# 2.net
KiCad netlist of a schematic drawn in EasyEDA Pro
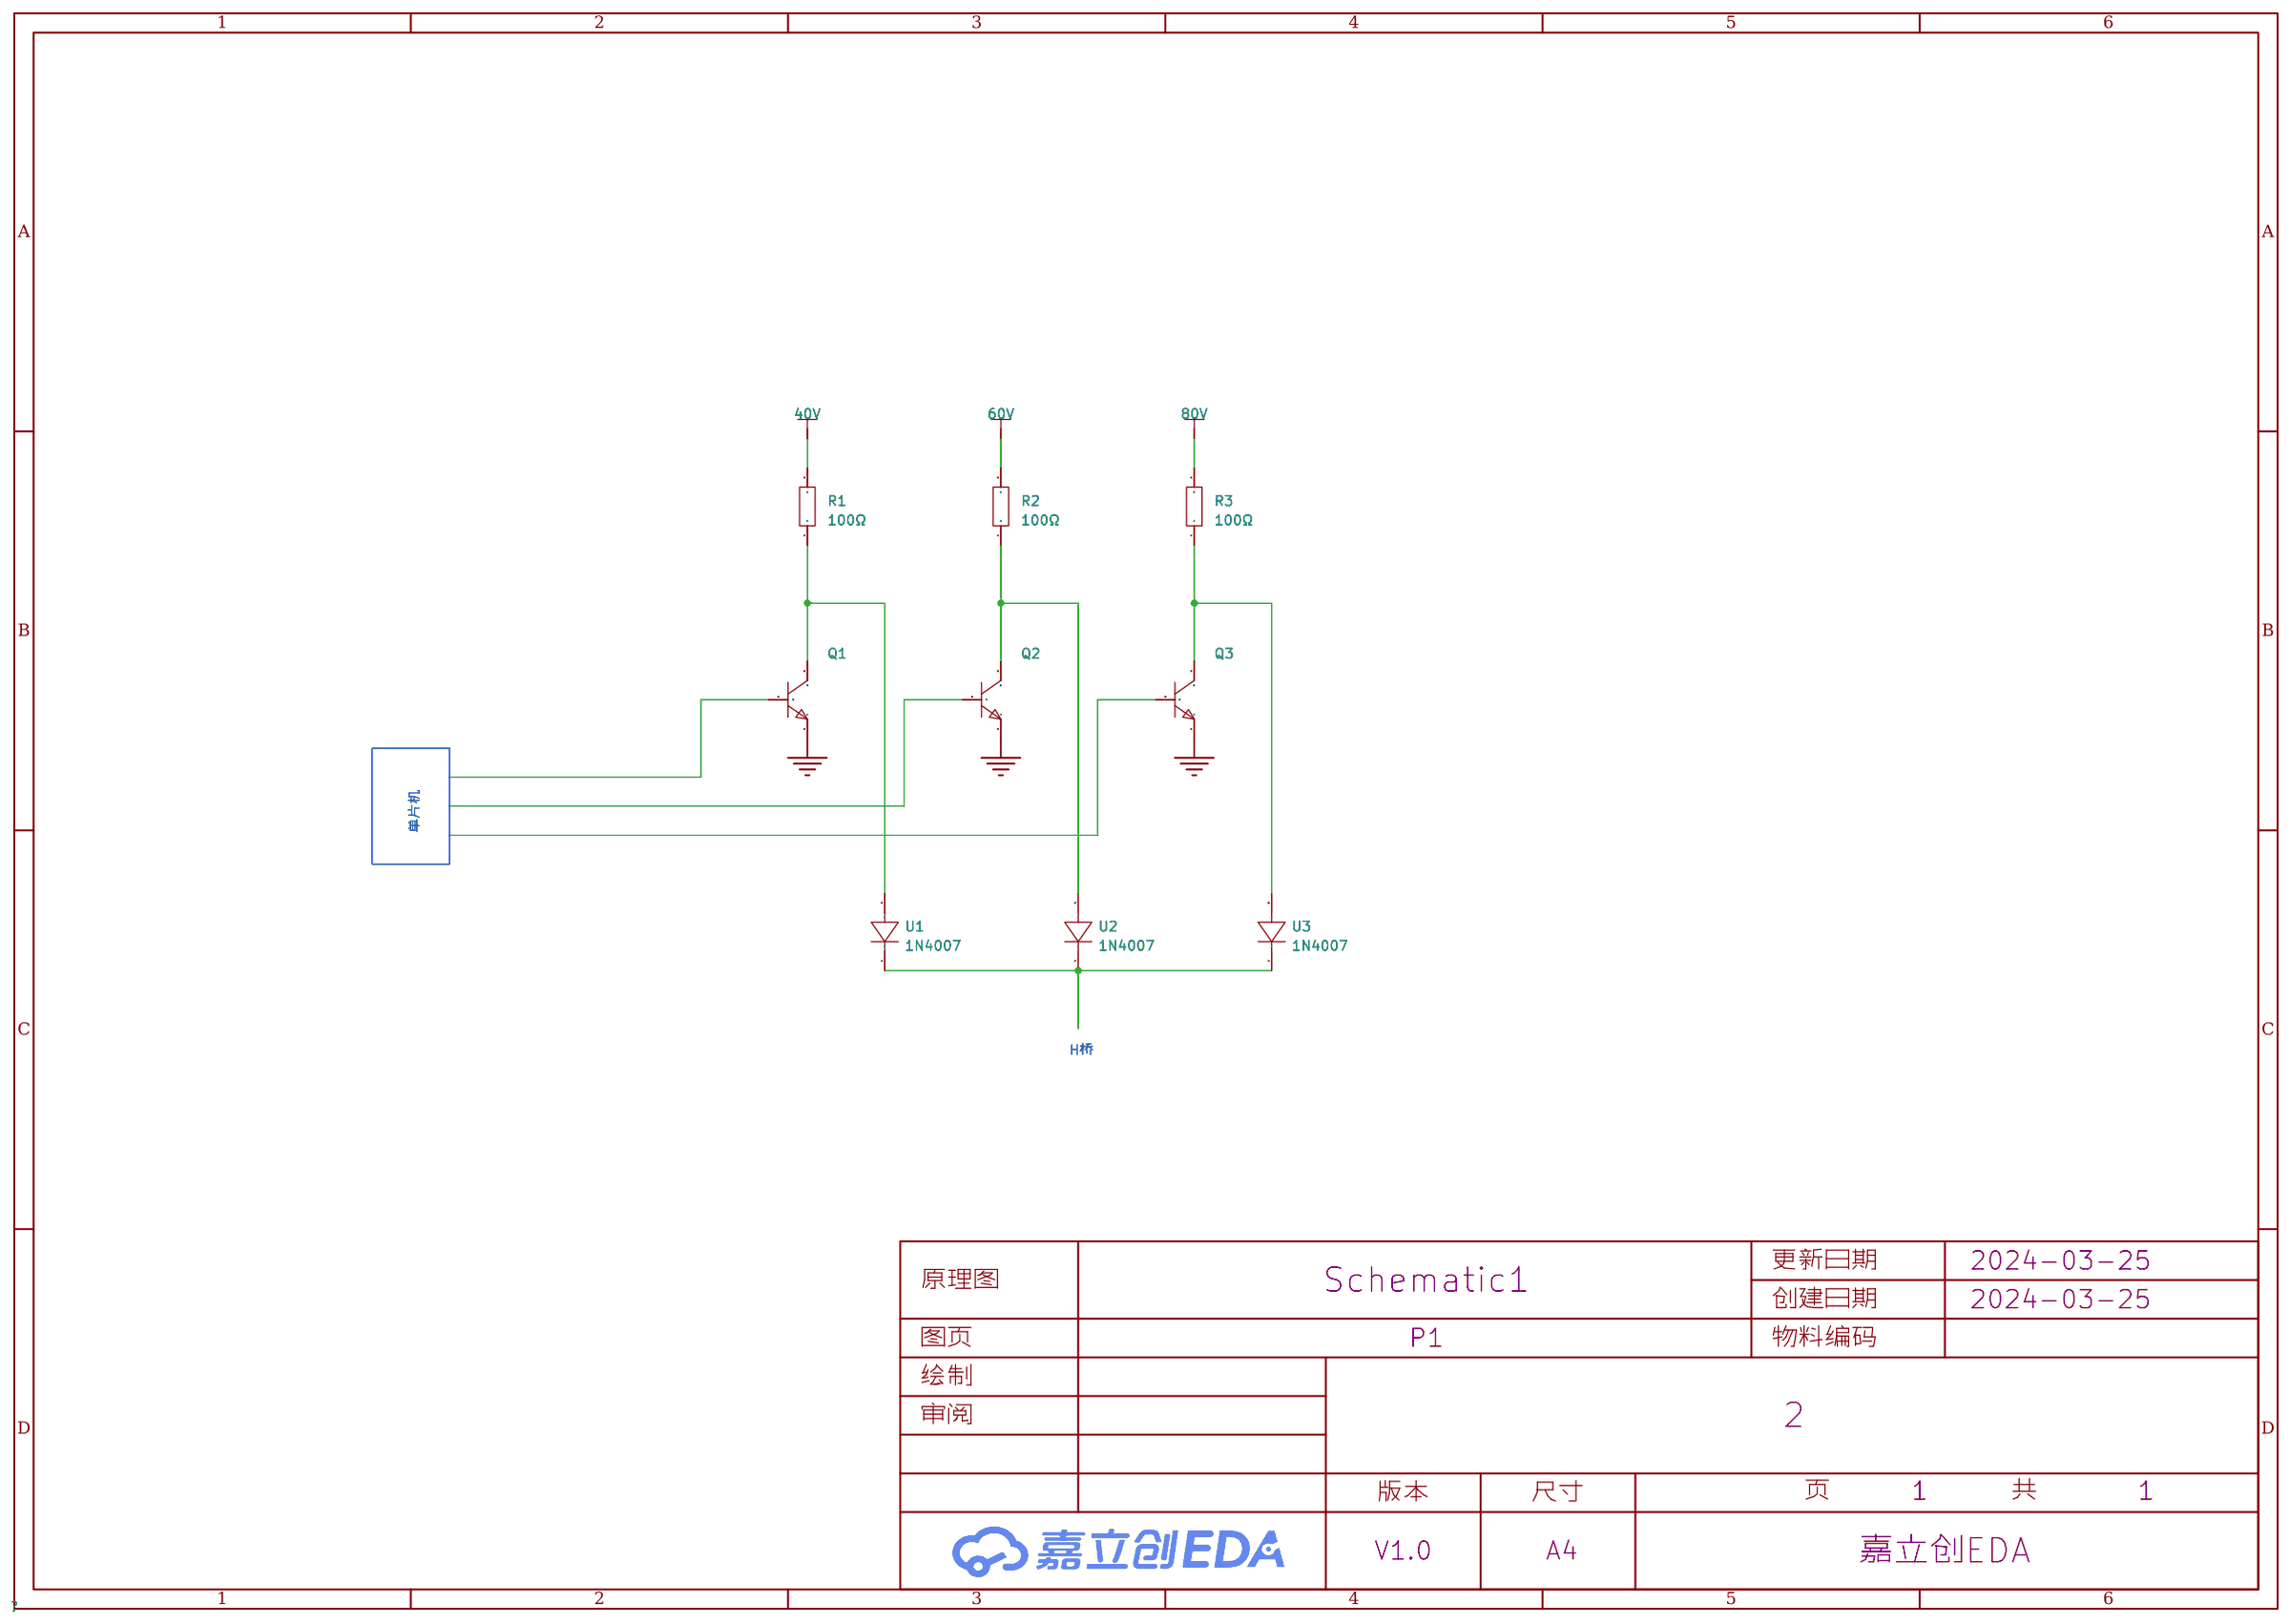
[diagram p0: schematic sheet]

(export (version "E")
  (design (tool "Eeschema 10.0.6"))
  (components
    (comp (ref "Q1")
      (value "~")
      (footprint "easyedapro:S8050_TO_92")
      (libsource (lib "easyedapro") (part "S8050_TO_NPN"))
    )
    (comp (ref "Q2")
      (value "~")
      (footprint "easyedapro:S8050_TO_92")
      (libsource (lib "easyedapro") (part "S8050_TO_NPN"))
    )
    (comp (ref "Q3")
      (value "~")
      (footprint "easyedapro:S8050_TO_92")
      (libsource (lib "easyedapro") (part "S8050_TO_NPN"))
    )
    (comp (ref "R1") (value "100Ω") (footprint "easyedapro:R0603") (libsource (lib "easyedapro") (part "电阻")))
    (comp (ref "R2") (value "100Ω") (footprint "easyedapro:R0603") (libsource (lib "easyedapro") (part "电阻")))
    (comp (ref "R3") (value "100Ω") (footprint "easyedapro:R0603") (libsource (lib "easyedapro") (part "电阻")))
    (comp (ref "U1")
      (value "1N4007")
      (footprint "easyedapro:SMA_L4.3-W2.6-LS5.1-RD")
      (libsource (lib "easyedapro") (part "1N4007_C9900004759"))
    )
    (comp (ref "U2")
      (value "1N4007")
      (footprint "easyedapro:SMA_L4.3-W2.6-LS5.1-RD")
      (libsource (lib "easyedapro") (part "1N4007_C9900004759"))
    )
    (comp (ref "U3")
      (value "1N4007")
      (footprint "easyedapro:SMA_L4.3-W2.6-LS5.1-RD")
      (libsource (lib "easyedapro") (part "1N4007_C9900004759"))
    )
  )
  (nets
    (net (code "1") (name "40V") (class "Default")
      (node (ref "R1") (pin "2") (pinfunction "2_2") (pintype "input"))
    )
    (net (code "2") (name "60V") (class "Default")
      (node (ref "R2") (pin "2") (pinfunction "2_2") (pintype "input"))
    )
    (net (code "3") (name "80V") (class "Default")
      (node (ref "R3") (pin "2") (pinfunction "2_2") (pintype "input"))
    )
    (net (code "4") (name "GND") (class "Default")
      (node (ref "Q1") (pin "1") (pinfunction "E_1") (pintype "unspecified"))
      (node (ref "Q2") (pin "1") (pinfunction "E_1") (pintype "unspecified"))
      (node (ref "Q3") (pin "1") (pinfunction "E_1") (pintype "unspecified"))
    )
    (net (code "5") (name "Net-(Q1-C)") (class "Default")
      (node (ref "Q1") (pin "3") (pinfunction "C_3") (pintype "unspecified"))
      (node (ref "R1") (pin "1") (pinfunction "1_1") (pintype "input"))
      (node (ref "U1") (pin "2") (pinfunction "A_2") (pintype "input"))
    )
    (net (code "6") (name "Net-(Q2-C)") (class "Default")
      (node (ref "Q2") (pin "3") (pinfunction "C_3") (pintype "unspecified"))
      (node (ref "R2") (pin "1") (pinfunction "1_1") (pintype "input"))
      (node (ref "U2") (pin "2") (pinfunction "A_2") (pintype "input"))
    )
    (net (code "7") (name "Net-(Q3-C)") (class "Default")
      (node (ref "Q3") (pin "3") (pinfunction "C_3") (pintype "unspecified"))
      (node (ref "R3") (pin "1") (pinfunction "1_1") (pintype "input"))
      (node (ref "U3") (pin "2") (pinfunction "A_2") (pintype "input"))
    )
    (net (code "8") (name "Net-(U1-K)") (class "Default")
      (node (ref "U1") (pin "1") (pinfunction "K_1") (pintype "input"))
      (node (ref "U2") (pin "1") (pinfunction "K_1") (pintype "input"))
      (node (ref "U3") (pin "1") (pinfunction "K_1") (pintype "input"))
    )
    (net (code "9") (name "unconnected-(Q1-B-Pad2)") (class "Default")
      (node (ref "Q1") (pin "2") (pinfunction "B_2") (pintype "unspecified"))
    )
    (net (code "10") (name "unconnected-(Q2-B-Pad2)") (class "Default")
      (node (ref "Q2") (pin "2") (pinfunction "B_2") (pintype "unspecified"))
    )
    (net (code "11") (name "unconnected-(Q3-B-Pad2)") (class "Default")
      (node (ref "Q3") (pin "2") (pinfunction "B_2") (pintype "unspecified"))
    )
  )
)
